# output_max10.net
KiCad netlist of a schematic drawn in EAGLE
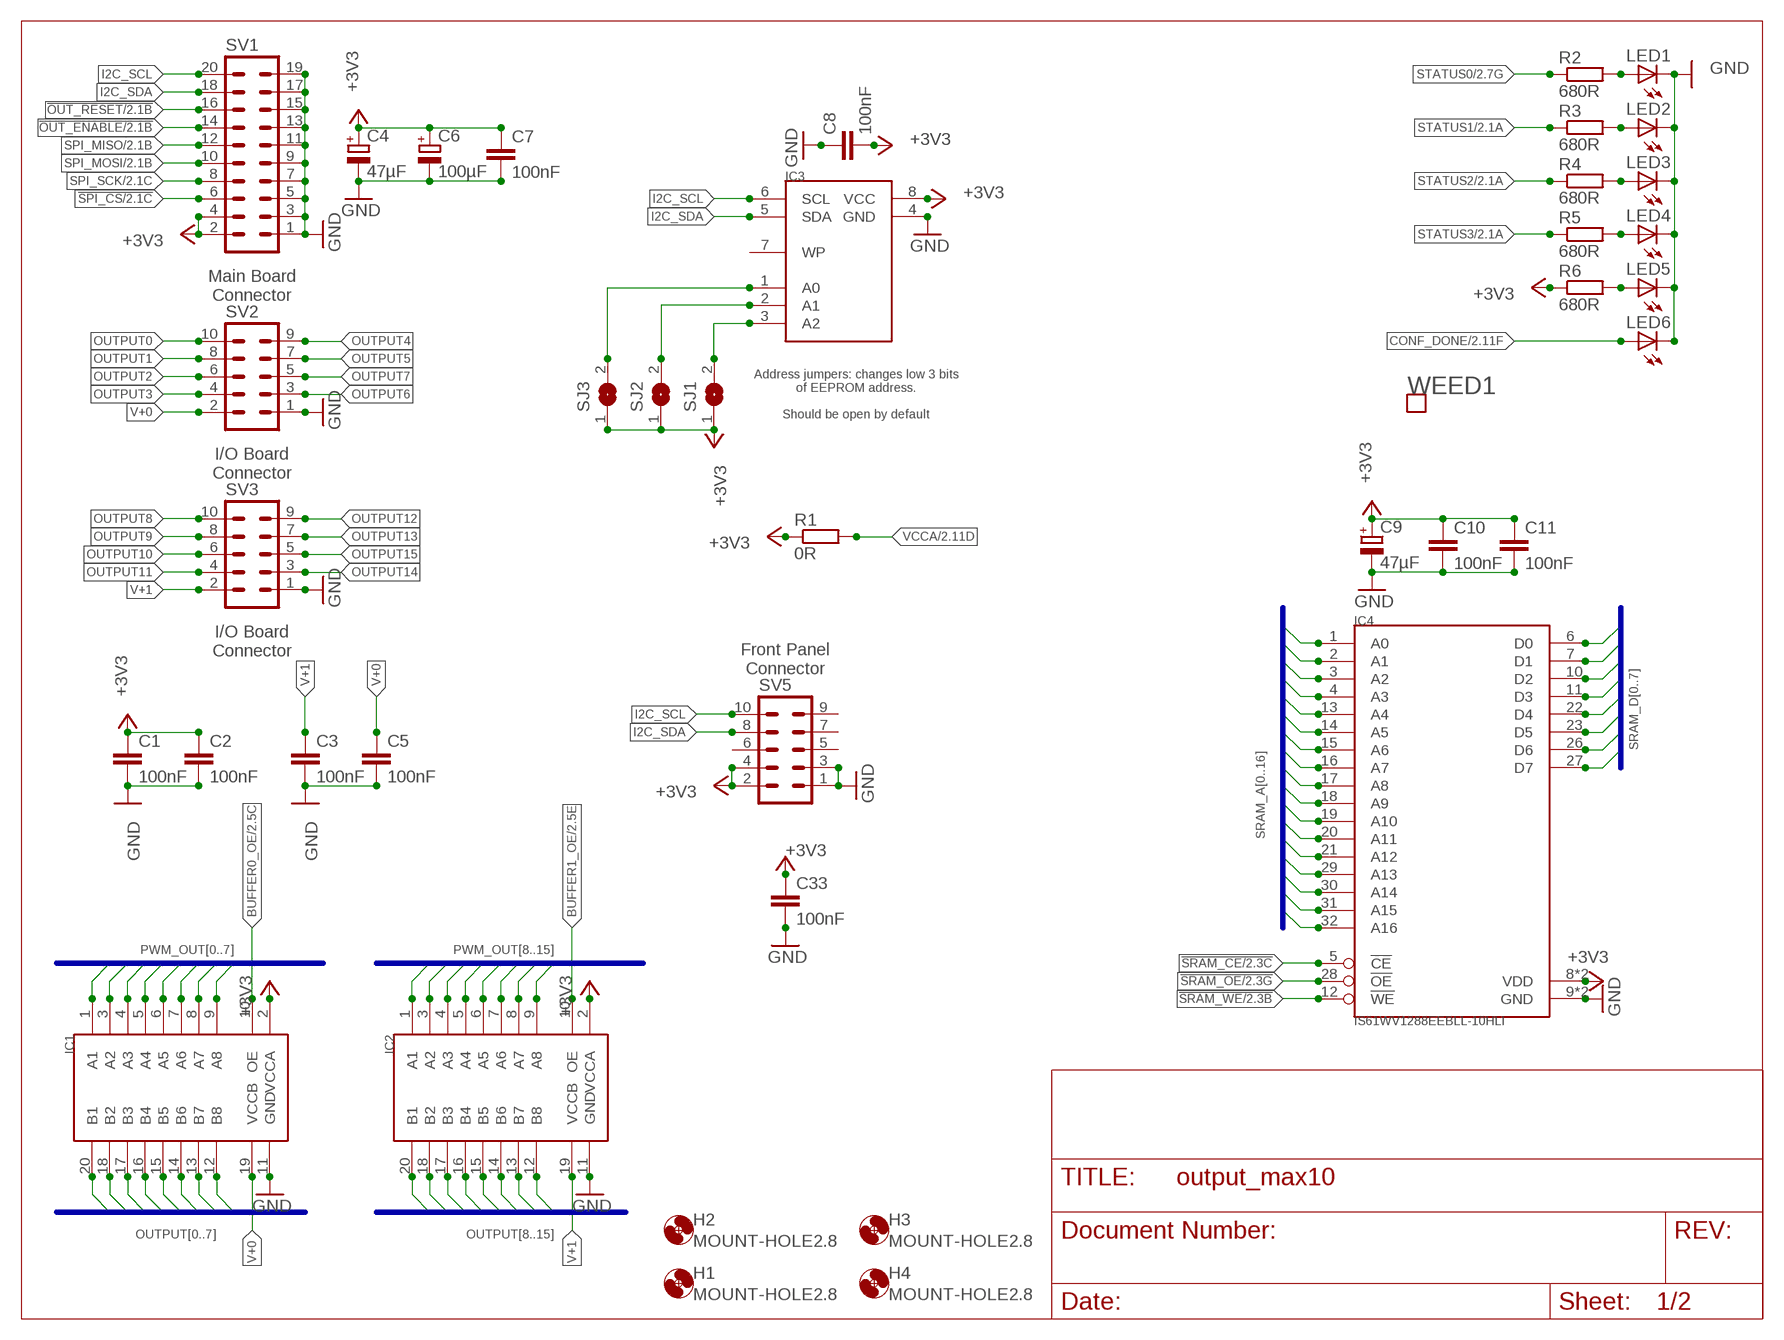
[diagram p0: schematic, sheet 1]
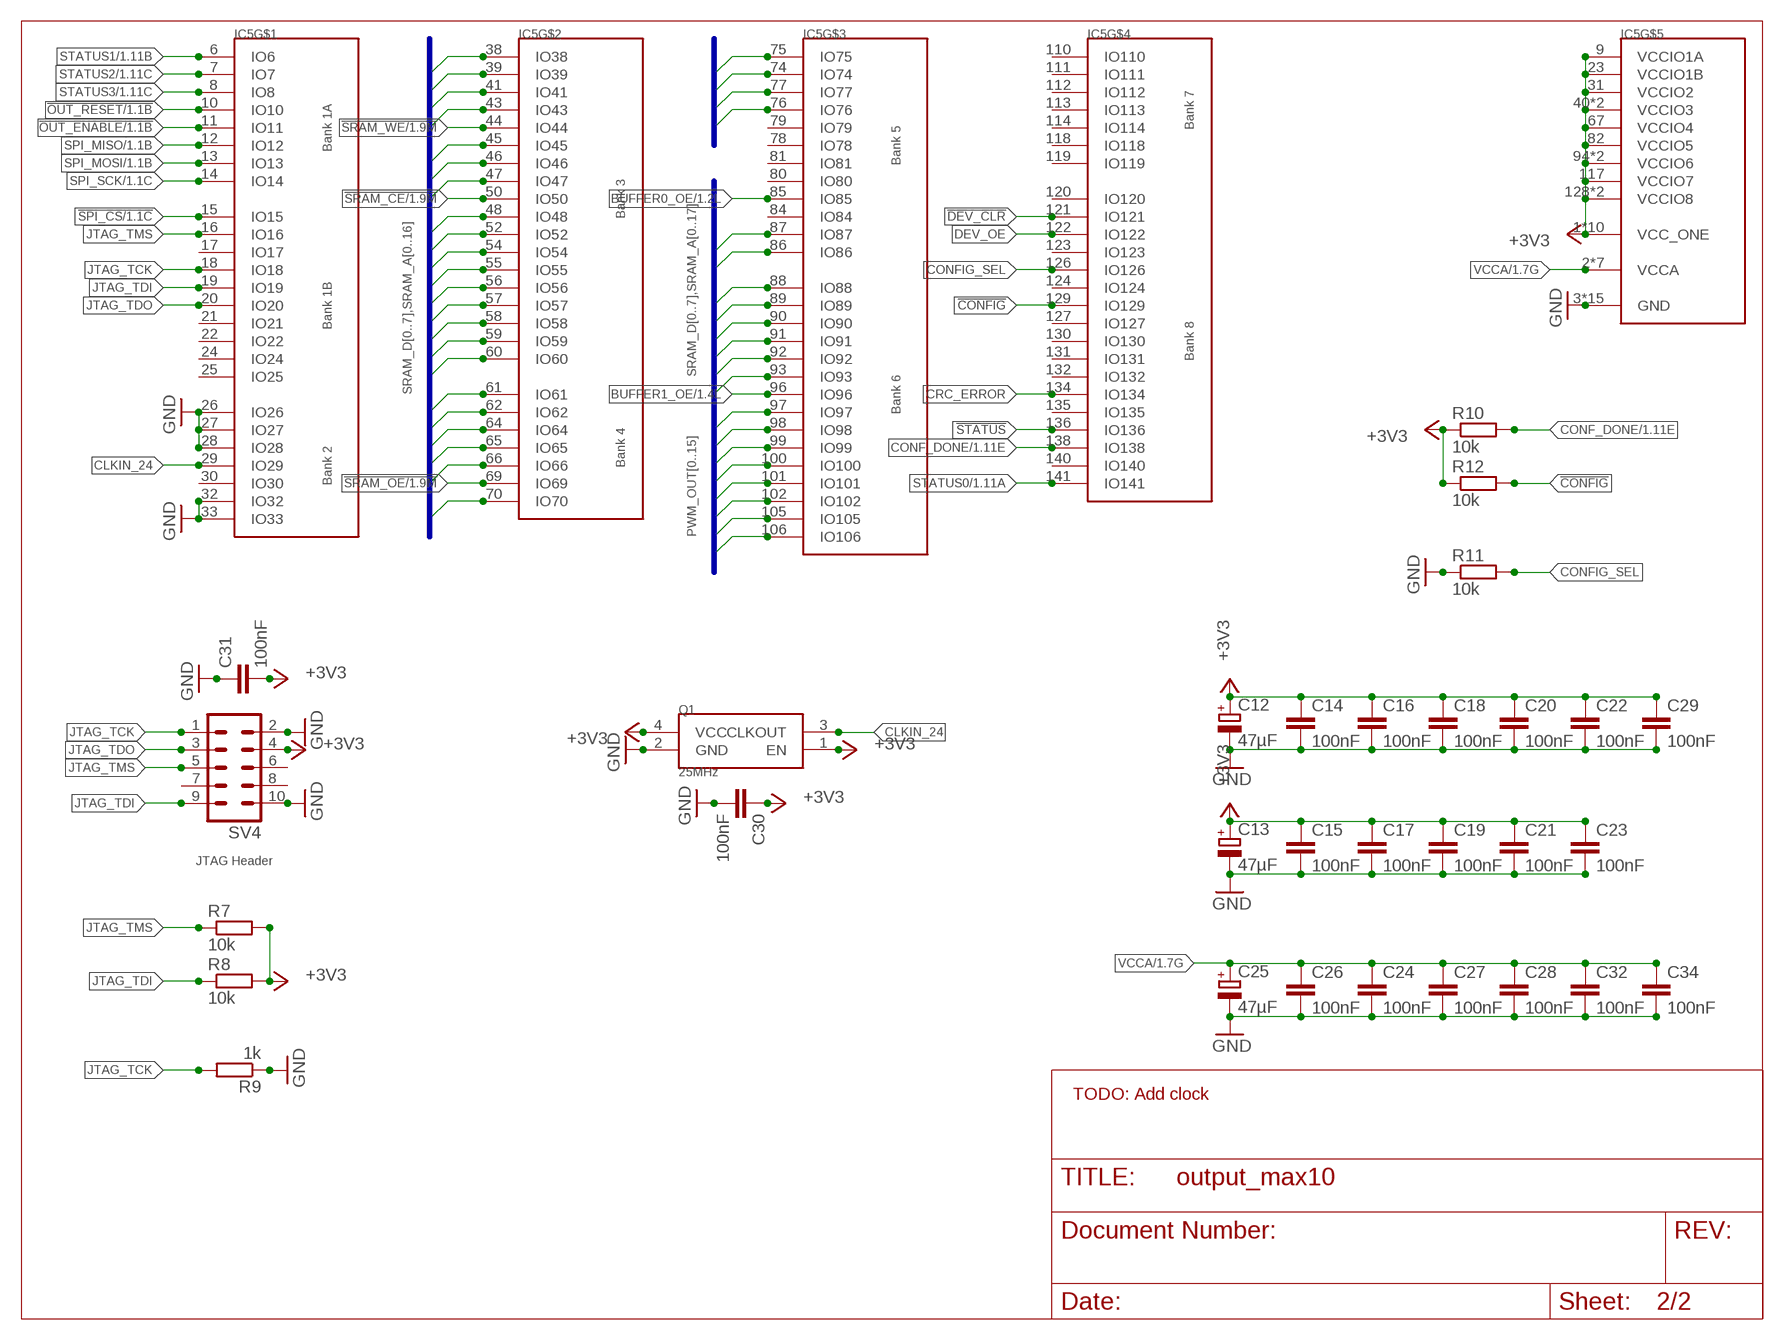
[diagram p1: schematic, sheet 2]

(export (version "E")
  (design (tool "Eeschema 10.0.6"))
  (components
    (comp (ref "C1")
      (value "100nF")
      (footprint "eagle-import:C0805")
      (libsource (lib "eagle-import") (part "C-EUC0805"))
    )
    (comp (ref "C2")
      (value "100nF")
      (footprint "eagle-import:C0805")
      (libsource (lib "eagle-import") (part "C-EUC0805"))
    )
    (comp (ref "C3")
      (value "100nF")
      (footprint "eagle-import:C0805")
      (libsource (lib "eagle-import") (part "C-EUC0805"))
    )
    (comp (ref "C4")
      (value "47µF")
      (footprint "eagle-import:CT7343")
      (libsource (lib "eagle-import") (part "CPOL-EUCT7343"))
    )
    (comp (ref "C5")
      (value "100nF")
      (footprint "eagle-import:C0805")
      (libsource (lib "eagle-import") (part "C-EUC0805"))
    )
    (comp (ref "C6")
      (value "100µF")
      (footprint "eagle-import:CT7343")
      (libsource (lib "eagle-import") (part "CPOL-EUCT7343"))
    )
    (comp (ref "C7")
      (value "100nF")
      (footprint "eagle-import:C0805")
      (libsource (lib "eagle-import") (part "C-EUC0805"))
    )
    (comp (ref "C8")
      (value "100nF")
      (footprint "eagle-import:C0805")
      (libsource (lib "eagle-import") (part "C-EUC0805"))
    )
    (comp (ref "C9")
      (value "47µF")
      (footprint "eagle-import:CT7343")
      (libsource (lib "eagle-import") (part "CPOL-EUCT7343"))
    )
    (comp (ref "C10")
      (value "100nF")
      (footprint "eagle-import:C0805")
      (libsource (lib "eagle-import") (part "C-EUC0805"))
    )
    (comp (ref "C11")
      (value "100nF")
      (footprint "eagle-import:C0805")
      (libsource (lib "eagle-import") (part "C-EUC0805"))
    )
    (comp (ref "C33")
      (value "100nF")
      (footprint "eagle-import:C0805")
      (libsource (lib "eagle-import") (part "C-EUC0805"))
    )
    (comp (ref "H1")
      (value "MOUNT-HOLE2.8")
      (footprint "eagle-import:2,8")
      (libsource (lib "eagle-import") (part "MOUNT-HOLE2.8"))
    )
    (comp (ref "H2")
      (value "MOUNT-HOLE2.8")
      (footprint "eagle-import:2,8")
      (libsource (lib "eagle-import") (part "MOUNT-HOLE2.8"))
    )
    (comp (ref "H3")
      (value "MOUNT-HOLE2.8")
      (footprint "eagle-import:2,8")
      (libsource (lib "eagle-import") (part "MOUNT-HOLE2.8"))
    )
    (comp (ref "H4")
      (value "MOUNT-HOLE2.8")
      (footprint "eagle-import:2,8")
      (libsource (lib "eagle-import") (part "MOUNT-HOLE2.8"))
    )
    (comp (ref "IC1")
      (value "TXB0108TSSOP20")
      (footprint "eagle-import:TSSOP20")
      (libsource (lib "eagle-import") (part "TXB0108TSSOP20"))
    )
    (comp (ref "IC2")
      (value "TXB0108TSSOP20")
      (footprint "eagle-import:TSSOP20")
      (libsource (lib "eagle-import") (part "TXB0108TSSOP20"))
    )
    (comp (ref "IC3")
      (value "AT24C02DSOIC-8")
      (footprint "eagle-import:SOIC8")
      (libsource (lib "eagle-import") (part "AT24C02DSOIC-8"))
    )
    (comp (ref "IC4")
      (value "IS61WV1288EEBLL-10HLI")
      (footprint "eagle-import:TSOP8X16")
      (libsource (lib "eagle-import") (part "IS61WV1288EEBLLTSOP32-I"))
    )
    (comp (ref "LED1")
      (value "LEDCHIPLED_1206")
      (footprint "eagle-import:CHIPLED_1206")
      (libsource (lib "eagle-import") (part "LEDCHIPLED_1206"))
    )
    (comp (ref "LED2")
      (value "LEDCHIPLED_1206")
      (footprint "eagle-import:CHIPLED_1206")
      (libsource (lib "eagle-import") (part "LEDCHIPLED_1206"))
    )
    (comp (ref "LED3")
      (value "LEDCHIPLED_1206")
      (footprint "eagle-import:CHIPLED_1206")
      (libsource (lib "eagle-import") (part "LEDCHIPLED_1206"))
    )
    (comp (ref "LED4")
      (value "LEDCHIPLED_1206")
      (footprint "eagle-import:CHIPLED_1206")
      (libsource (lib "eagle-import") (part "LEDCHIPLED_1206"))
    )
    (comp (ref "LED5")
      (value "LEDCHIPLED_1206")
      (footprint "eagle-import:CHIPLED_1206")
      (libsource (lib "eagle-import") (part "LEDCHIPLED_1206"))
    )
    (comp (ref "LED6")
      (value "LEDCHIPLED_1206")
      (footprint "eagle-import:CHIPLED_1206")
      (libsource (lib "eagle-import") (part "LEDCHIPLED_1206"))
    )
    (comp (ref "R1")
      (value "0R")
      (footprint "eagle-import:R2012")
      (libsource (lib "eagle-import") (part "R-EU_R2012"))
    )
    (comp (ref "R2")
      (value "680R")
      (footprint "eagle-import:M0805")
      (libsource (lib "eagle-import") (part "R-EU_M0805"))
    )
    (comp (ref "R3")
      (value "680R")
      (footprint "eagle-import:M0805")
      (libsource (lib "eagle-import") (part "R-EU_M0805"))
    )
    (comp (ref "R4")
      (value "680R")
      (footprint "eagle-import:M0805")
      (libsource (lib "eagle-import") (part "R-EU_M0805"))
    )
    (comp (ref "R5")
      (value "680R")
      (footprint "eagle-import:M0805")
      (libsource (lib "eagle-import") (part "R-EU_M0805"))
    )
    (comp (ref "R6")
      (value "680R")
      (footprint "eagle-import:M0805")
      (libsource (lib "eagle-import") (part "R-EU_M0805"))
    )
    (comp (ref "SJ1") (value "SJ") (footprint "eagle-import:SJ") (libsource (lib "eagle-import") (part "SJ")))
    (comp (ref "SJ2") (value "SJ") (footprint "eagle-import:SJ") (libsource (lib "eagle-import") (part "SJ")))
    (comp (ref "SJ3") (value "SJ") (footprint "eagle-import:SJ") (libsource (lib "eagle-import") (part "SJ")))
    (comp (ref "SV1")
      (value "MA10-2")
      (footprint "eagle-import:MA10-2")
      (libsource (lib "eagle-import") (part "MA10-2"))
    )
    (comp (ref "SV2")
      (value "MA05-2")
      (footprint "eagle-import:MA05-2")
      (libsource (lib "eagle-import") (part "MA05-2"))
    )
    (comp (ref "SV3")
      (value "MA05-2")
      (footprint "eagle-import:MA05-2")
      (libsource (lib "eagle-import") (part "MA05-2"))
    )
    (comp (ref "SV5")
      (value "MA05-2")
      (footprint "eagle-import:MA05-2")
      (libsource (lib "eagle-import") (part "MA05-2"))
    )
    (comp (ref "WEED1")
      (value "WEED")
      (footprint "eagle-import:DOINK")
      (libsource (lib "eagle-import") (part "WEED"))
    )
    (comp (ref "C12")
      (value "47µF")
      (footprint "eagle-import:CT7343")
      (libsource (lib "eagle-import") (part "CPOL-EUCT7343"))
    )
    (comp (ref "C13")
      (value "47µF")
      (footprint "eagle-import:CT7343")
      (libsource (lib "eagle-import") (part "CPOL-EUCT7343"))
    )
    (comp (ref "C14")
      (value "100nF")
      (footprint "eagle-import:C0805")
      (libsource (lib "eagle-import") (part "C-EUC0805"))
    )
    (comp (ref "C15")
      (value "100nF")
      (footprint "eagle-import:C0805")
      (libsource (lib "eagle-import") (part "C-EUC0805"))
    )
    (comp (ref "C16")
      (value "100nF")
      (footprint "eagle-import:C0805")
      (libsource (lib "eagle-import") (part "C-EUC0805"))
    )
    (comp (ref "C17")
      (value "100nF")
      (footprint "eagle-import:C0805")
      (libsource (lib "eagle-import") (part "C-EUC0805"))
    )
    (comp (ref "C18")
      (value "100nF")
      (footprint "eagle-import:C0805")
      (libsource (lib "eagle-import") (part "C-EUC0805"))
    )
    (comp (ref "C19")
      (value "100nF")
      (footprint "eagle-import:C0805")
      (libsource (lib "eagle-import") (part "C-EUC0805"))
    )
    (comp (ref "C20")
      (value "100nF")
      (footprint "eagle-import:C0805")
      (libsource (lib "eagle-import") (part "C-EUC0805"))
    )
    (comp (ref "C21")
      (value "100nF")
      (footprint "eagle-import:C0805")
      (libsource (lib "eagle-import") (part "C-EUC0805"))
    )
    (comp (ref "C22")
      (value "100nF")
      (footprint "eagle-import:C0805")
      (libsource (lib "eagle-import") (part "C-EUC0805"))
    )
    (comp (ref "C23")
      (value "100nF")
      (footprint "eagle-import:C0805")
      (libsource (lib "eagle-import") (part "C-EUC0805"))
    )
    (comp (ref "C24")
      (value "100nF")
      (footprint "eagle-import:C0805")
      (libsource (lib "eagle-import") (part "C-EUC0805"))
    )
    (comp (ref "C25")
      (value "47µF")
      (footprint "eagle-import:CT7343")
      (libsource (lib "eagle-import") (part "CPOL-EUCT7343"))
    )
    (comp (ref "C26")
      (value "100nF")
      (footprint "eagle-import:C0805")
      (libsource (lib "eagle-import") (part "C-EUC0805"))
    )
    (comp (ref "C27")
      (value "100nF")
      (footprint "eagle-import:C0805")
      (libsource (lib "eagle-import") (part "C-EUC0805"))
    )
    (comp (ref "C28")
      (value "100nF")
      (footprint "eagle-import:C0805")
      (libsource (lib "eagle-import") (part "C-EUC0805"))
    )
    (comp (ref "C29")
      (value "100nF")
      (footprint "eagle-import:C0805")
      (libsource (lib "eagle-import") (part "C-EUC0805"))
    )
    (comp (ref "C30")
      (value "100nF")
      (footprint "eagle-import:C0805")
      (libsource (lib "eagle-import") (part "C-EUC0805"))
    )
    (comp (ref "C31")
      (value "100nF")
      (footprint "eagle-import:C0805")
      (libsource (lib "eagle-import") (part "C-EUC0805"))
    )
    (comp (ref "C32")
      (value "100nF")
      (footprint "eagle-import:C0805")
      (libsource (lib "eagle-import") (part "C-EUC0805"))
    )
    (comp (ref "C34")
      (value "100nF")
      (footprint "eagle-import:C0805")
      (libsource (lib "eagle-import") (part "C-EUC0805"))
    )
    (comp (ref "IC5")
      (value "10M04EQFP144")
      (footprint "eagle-import:EQFP144")
      (fields (field (name "MOUSER") "989-10M04SCE144C8G"))
      (libsource (lib "eagle-import") (part "10M04EQFP144"))
    )
    (comp (ref "Q1")
      (value "25MHz")
      (footprint "eagle-import:VLGA-4")
      (libsource (lib "eagle-import") (part "DSC61XX"))
    )
    (comp (ref "R7")
      (value "10k")
      (footprint "eagle-import:M0805")
      (libsource (lib "eagle-import") (part "R-EU_M0805"))
    )
    (comp (ref "R8")
      (value "10k")
      (footprint "eagle-import:M0805")
      (libsource (lib "eagle-import") (part "R-EU_M0805"))
    )
    (comp (ref "R9")
      (value "1k")
      (footprint "eagle-import:M0805")
      (libsource (lib "eagle-import") (part "R-EU_M0805"))
    )
    (comp (ref "R10")
      (value "10k")
      (footprint "eagle-import:M0805")
      (libsource (lib "eagle-import") (part "R-EU_M0805"))
    )
    (comp (ref "R11")
      (value "10k")
      (footprint "eagle-import:M0805")
      (libsource (lib "eagle-import") (part "R-EU_M0805"))
    )
    (comp (ref "R12")
      (value "10k")
      (footprint "eagle-import:M0805")
      (libsource (lib "eagle-import") (part "R-EU_M0805"))
    )
    (comp (ref "SV4")
      (value "MA05-2")
      (footprint "eagle-import:MA05-2")
      (libsource (lib "eagle-import") (part "MA05-2"))
    )
  )
  (nets
    (net (code "1") (name "+3V3") (class "Default")
      (node (ref "C1") (pin "1") (pinfunction "1_1") (pintype "passive"))
      (node (ref "C10") (pin "1") (pinfunction "1_1") (pintype "passive"))
      (node (ref "C11") (pin "1") (pinfunction "1_1") (pintype "passive"))
      (node (ref "C12") (pin "+") (pinfunction "+_+") (pintype "passive"))
      (node (ref "C13") (pin "+") (pinfunction "+_+") (pintype "passive"))
      (node (ref "C14") (pin "1") (pinfunction "1_1") (pintype "passive"))
      (node (ref "C15") (pin "1") (pinfunction "1_1") (pintype "passive"))
      (node (ref "C16") (pin "1") (pinfunction "1_1") (pintype "passive"))
      (node (ref "C17") (pin "1") (pinfunction "1_1") (pintype "passive"))
      (node (ref "C18") (pin "1") (pinfunction "1_1") (pintype "passive"))
      (node (ref "C19") (pin "1") (pinfunction "1_1") (pintype "passive"))
      (node (ref "C2") (pin "1") (pinfunction "1_1") (pintype "passive"))
      (node (ref "C20") (pin "1") (pinfunction "1_1") (pintype "passive"))
      (node (ref "C21") (pin "1") (pinfunction "1_1") (pintype "passive"))
      (node (ref "C22") (pin "1") (pinfunction "1_1") (pintype "passive"))
      (node (ref "C23") (pin "1") (pinfunction "1_1") (pintype "passive"))
      (node (ref "C29") (pin "1") (pinfunction "1_1") (pintype "passive"))
      (node (ref "C30") (pin "1") (pinfunction "1_1") (pintype "passive"))
      (node (ref "C31") (pin "2") (pinfunction "2_2") (pintype "passive"))
      (node (ref "C33") (pin "1") (pinfunction "1_1") (pintype "passive"))
      (node (ref "C4") (pin "+") (pinfunction "+_+") (pintype "passive"))
      (node (ref "C6") (pin "+") (pinfunction "+_+") (pintype "passive"))
      (node (ref "C7") (pin "1") (pinfunction "1_1") (pintype "passive"))
      (node (ref "C8") (pin "2") (pinfunction "2_2") (pintype "passive"))
      (node (ref "C9") (pin "+") (pinfunction "+_+") (pintype "passive"))
      (node (ref "IC1") (pin "2") (pinfunction "VCCA_2") (pintype "bidirectional"))
      (node (ref "IC2") (pin "2") (pinfunction "VCCA_2") (pintype "bidirectional"))
      (node (ref "IC3") (pin "8") (pinfunction "VCC_8") (pintype "power_in"))
      (node (ref "IC4") (pin "24") (pinfunction "VDD_24") (pintype "power_in"))
      (node (ref "IC4") (pin "8") (pinfunction "VDD_8") (pintype "power_in"))
      (node (ref "IC5") (pin "1") (pinfunction "VCC_ONE_1") (pintype "power_in"))
      (node (ref "IC5") (pin "103") (pinfunction "VCCIO6_103") (pintype "power_in"))
      (node (ref "IC5") (pin "108") (pinfunction "VCC_ONE_108") (pintype "power_in"))
      (node (ref "IC5") (pin "109") (pinfunction "VCC_ONE_109") (pintype "power_in"))
      (node (ref "IC5") (pin "115") (pinfunction "VCC_ONE_115") (pintype "power_in"))
      (node (ref "IC5") (pin "117") (pinfunction "VCCIO7_117") (pintype "power_in"))
      (node (ref "IC5") (pin "128") (pinfunction "VCCIO8_128") (pintype "power_in"))
      (node (ref "IC5") (pin "139") (pinfunction "VCCIO8_139") (pintype "power_in"))
      (node (ref "IC5") (pin "144") (pinfunction "VCC_ONE_144") (pintype "power_in"))
      (node (ref "IC5") (pin "23") (pinfunction "VCCIO1B_23") (pintype "power_in"))
      (node (ref "IC5") (pin "31") (pinfunction "VCCIO2_31") (pintype "power_in"))
      (node (ref "IC5") (pin "36") (pinfunction "VCC_ONE_36") (pintype "power_in"))
      (node (ref "IC5") (pin "37") (pinfunction "VCC_ONE_37") (pintype "power_in"))
      (node (ref "IC5") (pin "40") (pinfunction "VCCIO3_40") (pintype "power_in"))
      (node (ref "IC5") (pin "49") (pinfunction "VCCIO3_49") (pintype "power_in"))
      (node (ref "IC5") (pin "51") (pinfunction "VCC_ONE_51") (pintype "power_in"))
      (node (ref "IC5") (pin "67") (pinfunction "VCCIO4_67") (pintype "power_in"))
      (node (ref "IC5") (pin "72") (pinfunction "VCC_ONE_72") (pintype "power_in"))
      (node (ref "IC5") (pin "73") (pinfunction "VCC_ONE_73") (pintype "power_in"))
      (node (ref "IC5") (pin "82") (pinfunction "VCCIO5_82") (pintype "power_in"))
      (node (ref "IC5") (pin "9") (pinfunction "VCCIO1A_9") (pintype "power_in"))
      (node (ref "IC5") (pin "94") (pinfunction "VCCIO6_94") (pintype "power_in"))
      (node (ref "Q1") (pin "1") (pinfunction "EN_1") (pintype "bidirectional"))
      (node (ref "Q1") (pin "4") (pinfunction "VCC_4") (pintype "power_in"))
      (node (ref "R1") (pin "1") (pinfunction "1_1") (pintype "passive"))
      (node (ref "R10") (pin "1") (pinfunction "1_1") (pintype "passive"))
      (node (ref "R12") (pin "1") (pinfunction "1_1") (pintype "passive"))
      (node (ref "R6") (pin "1") (pinfunction "1_1") (pintype "passive"))
      (node (ref "R7") (pin "2") (pinfunction "2_2") (pintype "passive"))
      (node (ref "R8") (pin "2") (pinfunction "2_2") (pintype "passive"))
      (node (ref "SJ1") (pin "1") (pinfunction "1_1") (pintype "passive"))
      (node (ref "SJ2") (pin "1") (pinfunction "1_1") (pintype "passive"))
      (node (ref "SJ3") (pin "1") (pinfunction "1_1") (pintype "passive"))
      (node (ref "SV1") (pin "2") (pinfunction "2_2") (pintype "passive"))
      (node (ref "SV1") (pin "4") (pinfunction "4_4") (pintype "passive"))
      (node (ref "SV4") (pin "4") (pinfunction "4_4") (pintype "passive"))
      (node (ref "SV5") (pin "2") (pinfunction "2_2") (pintype "passive"))
      (node (ref "SV5") (pin "4") (pinfunction "4_4") (pintype "passive"))
    )
    (net (code "11") (name "BUFFER0_OE") (class "Default")
      (node (ref "IC1") (pin "10") (pinfunction "OE_10") (pintype "bidirectional"))
      (node (ref "IC5") (pin "85") (pinfunction "IO85_85") (pintype "bidirectional"))
    )
    (net (code "12") (name "BUFFER1_OE") (class "Default")
      (node (ref "IC2") (pin "10") (pinfunction "OE_10") (pintype "bidirectional"))
      (node (ref "IC5") (pin "96") (pinfunction "IO96_96") (pintype "bidirectional"))
    )
    (net (code "13") (name "CLKIN_24") (class "Default")
      (node (ref "IC5") (pin "29") (pinfunction "IO29_29") (pintype "bidirectional"))
      (node (ref "Q1") (pin "3") (pinfunction "CLKOUT_3") (pintype "bidirectional"))
    )
    (net (code "14") (name "CONFIG_SEL") (class "Default")
      (node (ref "IC5") (pin "126") (pinfunction "IO126_126") (pintype "bidirectional"))
      (node (ref "R11") (pin "2") (pinfunction "2_2") (pintype "passive"))
    )
    (net (code "15") (name "CONF_DONE") (class "Default")
      (node (ref "IC5") (pin "138") (pinfunction "IO138_138") (pintype "bidirectional"))
      (node (ref "LED6") (pin "A") (pinfunction "A_A") (pintype "passive"))
      (node (ref "R10") (pin "2") (pinfunction "2_2") (pintype "passive"))
    )
    (net (code "16") (name "CRC_ERROR") (class "Default")
      (node (ref "IC5") (pin "134") (pinfunction "IO134_134") (pintype "bidirectional"))
    )
    (net (code "17") (name "DEV_OE") (class "Default")
      (node (ref "IC5") (pin "122") (pinfunction "IO122_122") (pintype "bidirectional"))
    )
    (net (code "18") (name "GND") (class "Default")
      (node (ref "C1") (pin "2") (pinfunction "2_2") (pintype "passive"))
      (node (ref "C10") (pin "2") (pinfunction "2_2") (pintype "passive"))
      (node (ref "C11") (pin "2") (pinfunction "2_2") (pintype "passive"))
      (node (ref "C12") (pin "-") (pinfunction "-_-") (pintype "passive"))
      (node (ref "C13") (pin "-") (pinfunction "-_-") (pintype "passive"))
      (node (ref "C14") (pin "2") (pinfunction "2_2") (pintype "passive"))
      (node (ref "C15") (pin "2") (pinfunction "2_2") (pintype "passive"))
      (node (ref "C16") (pin "2") (pinfunction "2_2") (pintype "passive"))
      (node (ref "C17") (pin "2") (pinfunction "2_2") (pintype "passive"))
      (node (ref "C18") (pin "2") (pinfunction "2_2") (pintype "passive"))
      (node (ref "C19") (pin "2") (pinfunction "2_2") (pintype "passive"))
      (node (ref "C2") (pin "2") (pinfunction "2_2") (pintype "passive"))
      (node (ref "C20") (pin "2") (pinfunction "2_2") (pintype "passive"))
      (node (ref "C21") (pin "2") (pinfunction "2_2") (pintype "passive"))
      (node (ref "C22") (pin "2") (pinfunction "2_2") (pintype "passive"))
      (node (ref "C23") (pin "2") (pinfunction "2_2") (pintype "passive"))
      (node (ref "C24") (pin "2") (pinfunction "2_2") (pintype "passive"))
      (node (ref "C25") (pin "-") (pinfunction "-_-") (pintype "passive"))
      (node (ref "C26") (pin "2") (pinfunction "2_2") (pintype "passive"))
      (node (ref "C27") (pin "2") (pinfunction "2_2") (pintype "passive"))
      (node (ref "C28") (pin "2") (pinfunction "2_2") (pintype "passive"))
      (node (ref "C29") (pin "2") (pinfunction "2_2") (pintype "passive"))
      (node (ref "C3") (pin "2") (pinfunction "2_2") (pintype "passive"))
      (node (ref "C30") (pin "2") (pinfunction "2_2") (pintype "passive"))
      (node (ref "C31") (pin "1") (pinfunction "1_1") (pintype "passive"))
      (node (ref "C32") (pin "2") (pinfunction "2_2") (pintype "passive"))
      (node (ref "C33") (pin "2") (pinfunction "2_2") (pintype "passive"))
      (node (ref "C34") (pin "2") (pinfunction "2_2") (pintype "passive"))
      (node (ref "C4") (pin "-") (pinfunction "-_-") (pintype "passive"))
      (node (ref "C5") (pin "2") (pinfunction "2_2") (pintype "passive"))
      (node (ref "C6") (pin "-") (pinfunction "-_-") (pintype "passive"))
      (node (ref "C7") (pin "2") (pinfunction "2_2") (pintype "passive"))
      (node (ref "C8") (pin "1") (pinfunction "1_1") (pintype "passive"))
      (node (ref "C9") (pin "-") (pinfunction "-_-") (pintype "passive"))
      (node (ref "IC1") (pin "11") (pinfunction "GND_11") (pintype "bidirectional"))
      (node (ref "IC2") (pin "11") (pinfunction "GND_11") (pintype "bidirectional"))
      (node (ref "IC3") (pin "4") (pinfunction "GND_4") (pintype "power_in"))
      (node (ref "IC4") (pin "25") (pinfunction "GND_25") (pintype "power_in"))
      (node (ref "IC4") (pin "9") (pinfunction "GND_9") (pintype "power_in"))
      (node (ref "IC5") (pin "104") (pinfunction "GND_104") (pintype "power_in"))
      (node (ref "IC5") (pin "116") (pinfunction "GND_116") (pintype "power_in"))
      (node (ref "IC5") (pin "125") (pinfunction "GND_125") (pintype "power_in"))
      (node (ref "IC5") (pin "133") (pinfunction "GND_133") (pintype "power_in"))
      (node (ref "IC5") (pin "137") (pinfunction "GND_137") (pintype "power_in"))
      (node (ref "IC5") (pin "142") (pinfunction "GND_142") (pintype "power_in"))
      (node (ref "IC5") (pin "26") (pinfunction "IO26_26") (pintype "bidirectional"))
      (node (ref "IC5") (pin "27") (pinfunction "IO27_27") (pintype "bidirectional"))
      (node (ref "IC5") (pin "28") (pinfunction "IO28_28") (pintype "bidirectional"))
      (node (ref "IC5") (pin "3") (pinfunction "GND_3") (pintype "power_in"))
      (node (ref "IC5") (pin "32") (pinfunction "IO32_32") (pintype "bidirectional"))
      (node (ref "IC5") (pin "33") (pinfunction "IO33_33") (pintype "bidirectional"))
      (node (ref "IC5") (pin "4") (pinfunction "GND_4") (pintype "power_in"))
      (node (ref "IC5") (pin "42") (pinfunction "GND_42") (pintype "power_in"))
      (node (ref "IC5") (pin "53") (pinfunction "GND_53") (pintype "power_in"))
      (node (ref "IC5") (pin "63") (pinfunction "GND_63") (pintype "power_in"))
      (node (ref "IC5") (pin "68") (pinfunction "GND_68") (pintype "power_in"))
      (node (ref "IC5") (pin "83") (pinfunction "GND_83") (pintype "power_in"))
      (node (ref "IC5") (pin "95") (pinfunction "GND_95") (pintype "power_in"))
      (node (ref "IC5") (pin "PAD") (pinfunction "GND_PAD") (pintype "power_in"))
      (node (ref "LED1") (pin "C") (pinfunction "C_C") (pintype "passive"))
      (node (ref "LED2") (pin "C") (pinfunction "C_C") (pintype "passive"))
      (node (ref "LED3") (pin "C") (pinfunction "C_C") (pintype "passive"))
      (node (ref "LED4") (pin "C") (pinfunction "C_C") (pintype "passive"))
      (node (ref "LED5") (pin "C") (pinfunction "C_C") (pintype "passive"))
      (node (ref "LED6") (pin "C") (pinfunction "C_C") (pintype "passive"))
      (node (ref "Q1") (pin "2") (pinfunction "GND_2") (pintype "power_in"))
      (node (ref "R11") (pin "1") (pinfunction "1_1") (pintype "passive"))
      (node (ref "R9") (pin "1") (pinfunction "1_1") (pintype "passive"))
      (node (ref "SV1") (pin "1") (pinfunction "1_1") (pintype "passive"))
      (node (ref "SV1") (pin "11") (pinfunction "11_11") (pintype "passive"))
      (node (ref "SV1") (pin "13") (pinfunction "13_13") (pintype "passive"))
      (node (ref "SV1") (pin "15") (pinfunction "15_15") (pintype "passive"))
      (node (ref "SV1") (pin "17") (pinfunction "17_17") (pintype "passive"))
      (node (ref "SV1") (pin "19") (pinfunction "19_19") (pintype "passive"))
      (node (ref "SV1") (pin "3") (pinfunction "3_3") (pintype "passive"))
      (node (ref "SV1") (pin "5") (pinfunction "5_5") (pintype "passive"))
      (node (ref "SV1") (pin "7") (pinfunction "7_7") (pintype "passive"))
      (node (ref "SV1") (pin "9") (pinfunction "9_9") (pintype "passive"))
      (node (ref "SV2") (pin "1") (pinfunction "1_1") (pintype "passive"))
      (node (ref "SV3") (pin "1") (pinfunction "1_1") (pintype "passive"))
      (node (ref "SV4") (pin "10") (pinfunction "10_10") (pintype "passive"))
      (node (ref "SV4") (pin "2") (pinfunction "2_2") (pintype "passive"))
      (node (ref "SV5") (pin "1") (pinfunction "1_1") (pintype "passive"))
      (node (ref "SV5") (pin "3") (pinfunction "3_3") (pintype "passive"))
    )
    (net (code "19") (name "I2C_SCL") (class "Default")
      (node (ref "IC3") (pin "6") (pinfunction "SCL_6") (pintype "bidirectional"))
      (node (ref "SV1") (pin "20") (pinfunction "20_20") (pintype "passive"))
      (node (ref "SV5") (pin "10") (pinfunction "10_10") (pintype "passive"))
    )
    (net (code "20") (name "I2C_SDA") (class "Default")
      (node (ref "IC3") (pin "5") (pinfunction "SDA_5") (pintype "bidirectional"))
      (node (ref "SV1") (pin "18") (pinfunction "18_18") (pintype "passive"))
      (node (ref "SV5") (pin "8") (pinfunction "8_8") (pintype "passive"))
    )
    (net (code "21") (name "JTAG_TCK") (class "Default")
      (node (ref "IC5") (pin "18") (pinfunction "IO18_18") (pintype "bidirectional"))
      (node (ref "R9") (pin "2") (pinfunction "2_2") (pintype "passive"))
      (node (ref "SV4") (pin "1") (pinfunction "1_1") (pintype "passive"))
    )
    (net (code "22") (name "JTAG_TDI") (class "Default")
      (node (ref "IC5") (pin "19") (pinfunction "IO19_19") (pintype "bidirectional"))
      (node (ref "R8") (pin "1") (pinfunction "1_1") (pintype "passive"))
      (node (ref "SV4") (pin "9") (pinfunction "9_9") (pintype "passive"))
    )
    (net (code "23") (name "JTAG_TDO") (class "Default")
      (node (ref "IC5") (pin "20") (pinfunction "IO20_20") (pintype "bidirectional"))
      (node (ref "SV4") (pin "3") (pinfunction "3_3") (pintype "passive"))
    )
    (net (code "24") (name "JTAG_TMS") (class "Default")
      (node (ref "IC5") (pin "16") (pinfunction "IO16_16") (pintype "bidirectional"))
      (node (ref "R7") (pin "1") (pinfunction "1_1") (pintype "passive"))
      (node (ref "SV4") (pin "5") (pinfunction "5_5") (pintype "passive"))
    )
    (net (code "25") (name "Net-(IC3-A0)") (class "Default")
      (node (ref "IC3") (pin "1") (pinfunction "A0_1") (pintype "bidirectional"))
      (node (ref "SJ3") (pin "2") (pinfunction "2_2") (pintype "passive"))
    )
    (net (code "26") (name "Net-(IC3-A1)") (class "Default")
      (node (ref "IC3") (pin "2") (pinfunction "A1_2") (pintype "bidirectional"))
      (node (ref "SJ2") (pin "2") (pinfunction "2_2") (pintype "passive"))
    )
    (net (code "27") (name "Net-(IC3-A2)") (class "Default")
      (node (ref "IC3") (pin "3") (pinfunction "A2_3") (pintype "bidirectional"))
      (node (ref "SJ1") (pin "2") (pinfunction "2_2") (pintype "passive"))
    )
    (net (code "28") (name "Net-(LED1-PadA)") (class "Default")
      (node (ref "LED1") (pin "A") (pinfunction "A_A") (pintype "passive"))
      (node (ref "R2") (pin "2") (pinfunction "2_2") (pintype "passive"))
    )
    (net (code "29") (name "Net-(LED2-PadA)") (class "Default")
      (node (ref "LED2") (pin "A") (pinfunction "A_A") (pintype "passive"))
      (node (ref "R3") (pin "2") (pinfunction "2_2") (pintype "passive"))
    )
    (net (code "30") (name "Net-(LED3-PadA)") (class "Default")
      (node (ref "LED3") (pin "A") (pinfunction "A_A") (pintype "passive"))
      (node (ref "R4") (pin "2") (pinfunction "2_2") (pintype "passive"))
    )
    (net (code "31") (name "Net-(LED4-PadA)") (class "Default")
      (node (ref "LED4") (pin "A") (pinfunction "A_A") (pintype "passive"))
      (node (ref "R5") (pin "2") (pinfunction "2_2") (pintype "passive"))
    )
    (net (code "32") (name "Net-(LED5-PadA)") (class "Default")
      (node (ref "LED5") (pin "A") (pinfunction "A_A") (pintype "passive"))
      (node (ref "R6") (pin "2") (pinfunction "2_2") (pintype "passive"))
    )
    (net (code "33") (name "OUTPUT0") (class "Default")
      (node (ref "IC1") (pin "20") (pinfunction "B1_20") (pintype "bidirectional"))
      (node (ref "SV2") (pin "10") (pinfunction "10_10") (pintype "passive"))
    )
    (net (code "34") (name "OUTPUT1") (class "Default")
      (node (ref "IC1") (pin "18") (pinfunction "B2_18") (pintype "bidirectional"))
      (node (ref "SV2") (pin "8") (pinfunction "8_8") (pintype "passive"))
    )
    (net (code "35") (name "OUTPUT2") (class "Default")
      (node (ref "IC1") (pin "17") (pinfunction "B3_17") (pintype "bidirectional"))
      (node (ref "SV2") (pin "6") (pinfunction "6_6") (pintype "passive"))
    )
    (net (code "36") (name "OUTPUT3") (class "Default")
      (node (ref "IC1") (pin "16") (pinfunction "B4_16") (pintype "bidirectional"))
      (node (ref "SV2") (pin "4") (pinfunction "4_4") (pintype "passive"))
    )
    (net (code "37") (name "OUTPUT4") (class "Default")
      (node (ref "IC1") (pin "15") (pinfunction "B5_15") (pintype "bidirectional"))
      (node (ref "SV2") (pin "9") (pinfunction "9_9") (pintype "passive"))
    )
    (net (code "38") (name "OUTPUT5") (class "Default")
      (node (ref "IC1") (pin "14") (pinfunction "B6_14") (pintype "bidirectional"))
      (node (ref "SV2") (pin "7") (pinfunction "7_7") (pintype "passive"))
    )
    (net (code "39") (name "OUTPUT6") (class "Default")
      (node (ref "IC1") (pin "13") (pinfunction "B7_13") (pintype "bidirectional"))
      (node (ref "SV2") (pin "3") (pinfunction "3_3") (pintype "passive"))
    )
    (net (code "40") (name "OUTPUT7") (class "Default")
      (node (ref "IC1") (pin "12") (pinfunction "B8_12") (pintype "bidirectional"))
      (node (ref "SV2") (pin "5") (pinfunction "5_5") (pintype "passive"))
    )
    (net (code "41") (name "OUTPUT8") (class "Default")
      (node (ref "IC2") (pin "20") (pinfunction "B1_20") (pintype "bidirectional"))
      (node (ref "SV3") (pin "10") (pinfunction "10_10") (pintype "passive"))
    )
    (net (code "42") (name "OUTPUT9") (class "Default")
      (node (ref "IC2") (pin "18") (pinfunction "B2_18") (pintype "bidirectional"))
      (node (ref "SV3") (pin "8") (pinfunction "8_8") (pintype "passive"))
    )
    (net (code "43") (name "OUTPUT10") (class "Default")
      (node (ref "IC2") (pin "17") (pinfunction "B3_17") (pintype "bidirectional"))
      (node (ref "SV3") (pin "6") (pinfunction "6_6") (pintype "passive"))
    )
    (net (code "44") (name "OUTPUT11") (class "Default")
      (node (ref "IC2") (pin "16") (pinfunction "B4_16") (pintype "bidirectional"))
      (node (ref "SV3") (pin "4") (pinfunction "4_4") (pintype "passive"))
    )
    (net (code "45") (name "OUTPUT12") (class "Default")
      (node (ref "IC2") (pin "15") (pinfunction "B5_15") (pintype "bidirectional"))
      (node (ref "SV3") (pin "9") (pinfunction "9_9") (pintype "passive"))
    )
    (net (code "46") (name "OUTPUT13") (class "Default")
      (node (ref "IC2") (pin "14") (pinfunction "B6_14") (pintype "bidirectional"))
      (node (ref "SV3") (pin "7") (pinfunction "7_7") (pintype "passive"))
    )
    (net (code "47") (name "OUTPUT14") (class "Default")
      (node (ref "IC2") (pin "13") (pinfunction "B7_13") (pintype "bidirectional"))
      (node (ref "SV3") (pin "3") (pinfunction "3_3") (pintype "passive"))
    )
    (net (code "48") (name "OUTPUT15") (class "Default")
      (node (ref "IC2") (pin "12") (pinfunction "B8_12") (pintype "bidirectional"))
      (node (ref "SV3") (pin "5") (pinfunction "5_5") (pintype "passive"))
    )
    (net (code "49") (name "PWM_OUT0") (class "Default")
      (node (ref "IC1") (pin "9") (pinfunction "A8_9") (pintype "bidirectional"))
      (node (ref "IC5") (pin "86") (pinfunction "IO86_86") (pintype "bidirectional"))
    )
    (net (code "50") (name "PWM_OUT1") (class "Default")
      (node (ref "IC1") (pin "8") (pinfunction "A7_8") (pintype "bidirectional"))
      (node (ref "IC5") (pin "87") (pinfunction "IO87_87") (pintype "bidirectional"))
    )
    (net (code "51") (name "PWM_OUT2") (class "Default")
      (node (ref "IC1") (pin "7") (pinfunction "A6_7") (pintype "bidirectional"))
      (node (ref "IC5") (pin "88") (pinfunction "IO88_88") (pintype "bidirectional"))
    )
    (net (code "52") (name "PWM_OUT3") (class "Default")
      (node (ref "IC1") (pin "6") (pinfunction "A5_6") (pintype "bidirectional"))
      (node (ref "IC5") (pin "89") (pinfunction "IO89_89") (pintype "bidirectional"))
    )
    (net (code "53") (name "PWM_OUT4") (class "Default")
      (node (ref "IC1") (pin "5") (pinfunction "A4_5") (pintype "bidirectional"))
      (node (ref "IC5") (pin "90") (pinfunction "IO90_90") (pintype "bidirectional"))
    )
    (net (code "54") (name "PWM_OUT5") (class "Default")
      (node (ref "IC1") (pin "4") (pinfunction "A3_4") (pintype "bidirectional"))
      (node (ref "IC5") (pin "91") (pinfunction "IO91_91") (pintype "bidirectional"))
    )
    (net (code "55") (name "PWM_OUT6") (class "Default")
      (node (ref "IC1") (pin "3") (pinfunction "A2_3") (pintype "bidirectional"))
      (node (ref "IC5") (pin "92") (pinfunction "IO92_92") (pintype "bidirectional"))
    )
    (net (code "56") (name "PWM_OUT7") (class "Default")
      (node (ref "IC1") (pin "1") (pinfunction "A1_1") (pintype "bidirectional"))
      (node (ref "IC5") (pin "93") (pinfunction "IO93_93") (pintype "bidirectional"))
    )
    (net (code "57") (name "PWM_OUT8") (class "Default")
      (node (ref "IC2") (pin "9") (pinfunction "A8_9") (pintype "bidirectional"))
      (node (ref "IC5") (pin "97") (pinfunction "IO97_97") (pintype "bidirectional"))
    )
    (net (code "58") (name "PWM_OUT9") (class "Default")
      (node (ref "IC2") (pin "8") (pinfunction "A7_8") (pintype "bidirectional"))
      (node (ref "IC5") (pin "98") (pinfunction "IO98_98") (pintype "bidirectional"))
    )
    (net (code "59") (name "PWM_OUT10") (class "Default")
      (node (ref "IC2") (pin "7") (pinfunction "A6_7") (pintype "bidirectional"))
      (node (ref "IC5") (pin "99") (pinfunction "IO99_99") (pintype "bidirectional"))
    )
    (net (code "60") (name "PWM_OUT11") (class "Default")
      (node (ref "IC2") (pin "6") (pinfunction "A5_6") (pintype "bidirectional"))
      (node (ref "IC5") (pin "100") (pinfunction "IO100_100") (pintype "bidirectional"))
    )
    (net (code "61") (name "PWM_OUT12") (class "Default")
      (node (ref "IC2") (pin "5") (pinfunction "A4_5") (pintype "bidirectional"))
      (node (ref "IC5") (pin "101") (pinfunction "IO101_101") (pintype "bidirectional"))
    )
    (net (code "62") (name "PWM_OUT13") (class "Default")
      (node (ref "IC2") (pin "4") (pinfunction "A3_4") (pintype "bidirectional"))
      (node (ref "IC5") (pin "102") (pinfunction "IO102_102") (pintype "bidirectional"))
    )
    (net (code "63") (name "PWM_OUT14") (class "Default")
      (node (ref "IC2") (pin "3") (pinfunction "A2_3") (pintype "bidirectional"))
      (node (ref "IC5") (pin "105") (pinfunction "IO105_105") (pintype "bidirectional"))
    )
    (net (code "64") (name "PWM_OUT15") (class "Default")
      (node (ref "IC2") (pin "1") (pinfunction "A1_1") (pintype "bidirectional"))
      (node (ref "IC5") (pin "106") (pinfunction "IO106_106") (pintype "bidirectional"))
    )
    (net (code "65") (name "SPI_MISO") (class "Default")
      (node (ref "IC5") (pin "12") (pinfunction "IO12_12") (pintype "bidirectional"))
      (node (ref "SV1") (pin "12") (pinfunction "12_12") (pintype "passive"))
    )
    (net (code "66") (name "SPI_MOSI") (class "Default")
      (node (ref "IC5") (pin "13") (pinfunction "IO13_13") (pintype "bidirectional"))
      (node (ref "SV1") (pin "10") (pinfunction "10_10") (pintype "passive"))
    )
    (net (code "67") (name "SPI_SCK") (class "Default")
      (node (ref "IC5") (pin "14") (pinfunction "IO14_14") (pintype "bidirectional"))
      (node (ref "SV1") (pin "8") (pinfunction "8_8") (pintype "passive"))
    )
    (net (code "68") (name "SRAM_A0") (class "Default")
      (node (ref "IC4") (pin "1") (pinfunction "A0_1") (pintype "input"))
      (node (ref "IC5") (pin "56") (pinfunction "IO56_56") (pintype "bidirectional"))
    )
    (net (code "69") (name "SRAM_A1") (class "Default")
      (node (ref "IC4") (pin "2") (pinfunction "A1_2") (pintype "input"))
      (node (ref "IC5") (pin "55") (pinfunction "IO55_55") (pintype "bidirectional"))
    )
    (net (code "70") (name "SRAM_A2") (class "Default")
      (node (ref "IC4") (pin "3") (pinfunction "A2_3") (pintype "input"))
      (node (ref "IC5") (pin "54") (pinfunction "IO54_54") (pintype "bidirectional"))
    )
    (net (code "71") (name "SRAM_A3") (class "Default")
      (node (ref "IC4") (pin "4") (pinfunction "A3_4") (pintype "input"))
      (node (ref "IC5") (pin "52") (pinfunction "IO52_52") (pintype "bidirectional"))
    )
    (net (code "72") (name "SRAM_A4") (class "Default")
      (node (ref "IC4") (pin "13") (pinfunction "A4_13") (pintype "input"))
      (node (ref "IC5") (pin "43") (pinfunction "IO43_43") (pintype "bidirectional"))
    )
    (net (code "73") (name "SRAM_A5") (class "Default")
      (node (ref "IC4") (pin "14") (pinfunction "A5_14") (pintype "input"))
      (node (ref "IC5") (pin "41") (pinfunction "IO41_41") (pintype "bidirectional"))
    )
    (net (code "74") (name "SRAM_A6") (class "Default")
      (node (ref "IC4") (pin "15") (pinfunction "A6_15") (pintype "input"))
      (node (ref "IC5") (pin "39") (pinfunction "IO39_39") (pintype "bidirectional"))
    )
    (net (code "75") (name "SRAM_A7") (class "Default")
      (node (ref "IC4") (pin "16") (pinfunction "A7_16") (pintype "input"))
      (node (ref "IC5") (pin "38") (pinfunction "IO38_38") (pintype "bidirectional"))
    )
    (net (code "76") (name "SRAM_A8") (class "Default")
      (node (ref "IC4") (pin "17") (pinfunction "A8_17") (pintype "input"))
      (node (ref "IC5") (pin "57") (pinfunction "IO57_57") (pintype "bidirectional"))
    )
    (net (code "77") (name "SRAM_A9") (class "Default")
      (node (ref "IC4") (pin "18") (pinfunction "A9_18") (pintype "input"))
      (node (ref "IC5") (pin "58") (pinfunction "IO58_58") (pintype "bidirectional"))
    )
    (net (code "78") (name "SRAM_A10") (class "Default")
      (node (ref "IC4") (pin "19") (pinfunction "A10_19") (pintype "input"))
      (node (ref "IC5") (pin "59") (pinfunction "IO59_59") (pintype "bidirectional"))
    )
    (net (code "79") (name "SRAM_A11") (class "Default")
      (node (ref "IC4") (pin "20") (pinfunction "A11_20") (pintype "input"))
      (node (ref "IC5") (pin "60") (pinfunction "IO60_60") (pintype "bidirectional"))
    )
    (net (code "80") (name "SRAM_A12") (class "Default")
      (node (ref "IC4") (pin "21") (pinfunction "A12_21") (pintype "input"))
      (node (ref "IC5") (pin "61") (pinfunction "IO61_61") (pintype "bidirectional"))
    )
    (net (code "81") (name "SRAM_A13") (class "Default")
      (node (ref "IC4") (pin "29") (pinfunction "A13_29") (pintype "input"))
      (node (ref "IC5") (pin "70") (pinfunction "IO70_70") (pintype "bidirectional"))
    )
    (net (code "82") (name "SRAM_A14") (class "Default")
      (node (ref "IC4") (pin "30") (pinfunction "A14_30") (pintype "input"))
      (node (ref "IC5") (pin "76") (pinfunction "IO76_76") (pintype "bidirectional"))
    )
    (net (code "83") (name "SRAM_A15") (class "Default")
      (node (ref "IC4") (pin "31") (pinfunction "A15_31") (pintype "input"))
      (node (ref "IC5") (pin "75") (pinfunction "IO75_75") (pintype "bidirectional"))
    )
    (net (code "84") (name "SRAM_A16") (class "Default")
      (node (ref "IC4") (pin "32") (pinfunction "A16_32") (pintype "input"))
      (node (ref "IC5") (pin "74") (pinfunction "IO74_74") (pintype "bidirectional"))
    )
    (net (code "85") (name "SRAM_D0") (class "Default")
      (node (ref "IC4") (pin "6") (pinfunction "D0_6") (pintype "bidirectional"))
      (node (ref "IC5") (pin "48") (pinfunction "IO48_48") (pintype "bidirectional"))
    )
    (net (code "86") (name "SRAM_D1") (class "Default")
      (node (ref "IC4") (pin "7") (pinfunction "D1_7") (pintype "bidirectional"))
      (node (ref "IC5") (pin "47") (pinfunction "IO47_47") (pintype "bidirectional"))
    )
    (net (code "87") (name "SRAM_D2") (class "Default")
      (node (ref "IC4") (pin "10") (pinfunction "D2_10") (pintype "bidirectional"))
      (node (ref "IC5") (pin "46") (pinfunction "IO46_46") (pintype "bidirectional"))
    )
    (net (code "88") (name "SRAM_D3") (class "Default")
      (node (ref "IC4") (pin "11") (pinfunction "D3_11") (pintype "bidirectional"))
      (node (ref "IC5") (pin "45") (pinfunction "IO45_45") (pintype "bidirectional"))
    )
    (net (code "89") (name "SRAM_D4") (class "Default")
      (node (ref "IC4") (pin "22") (pinfunction "D4_22") (pintype "bidirectional"))
      (node (ref "IC5") (pin "62") (pinfunction "IO62_62") (pintype "bidirectional"))
    )
    (net (code "90") (name "SRAM_D5") (class "Default")
      (node (ref "IC4") (pin "23") (pinfunction "D5_23") (pintype "bidirectional"))
      (node (ref "IC5") (pin "64") (pinfunction "IO64_64") (pintype "bidirectional"))
    )
    (net (code "91") (name "SRAM_D6") (class "Default")
      (node (ref "IC4") (pin "26") (pinfunction "D6_26") (pintype "bidirectional"))
      (node (ref "IC5") (pin "65") (pinfunction "IO65_65") (pintype "bidirectional"))
    )
    (net (code "92") (name "SRAM_D7") (class "Default")
      (node (ref "IC4") (pin "27") (pinfunction "D7_27") (pintype "bidirectional"))
      (node (ref "IC5") (pin "66") (pinfunction "IO66_66") (pintype "bidirectional"))
    )
    (net (code "93") (name "STATUS0") (class "Default")
      (node (ref "IC5") (pin "141") (pinfunction "IO141_141") (pintype "bidirectional"))
      (node (ref "R2") (pin "1") (pinfunction "1_1") (pintype "passive"))
    )
    (net (code "94") (name "STATUS1") (class "Default")
      (node (ref "IC5") (pin "6") (pinfunction "IO6_6") (pintype "bidirectional"))
      (node (ref "R3") (pin "1") (pinfunction "1_1") (pintype "passive"))
    )
    (net (code "95") (name "STATUS2") (class "Default")
      (node (ref "IC5") (pin "7") (pinfunction "IO7_7") (pintype "bidirectional"))
      (node (ref "R4") (pin "1") (pinfunction "1_1") (pintype "passive"))
    )
    (net (code "96") (name "STATUS3") (class "Default")
      (node (ref "IC5") (pin "8") (pinfunction "IO8_8") (pintype "bidirectional"))
      (node (ref "R5") (pin "1") (pinfunction "1_1") (pintype "passive"))
    )
    (net (code "97") (name "V+0") (class "Default")
      (node (ref "C5") (pin "1") (pinfunction "1_1") (pintype "passive"))
      (node (ref "IC1") (pin "19") (pinfunction "VCCB_19") (pintype "bidirectional"))
      (node (ref "SV2") (pin "2") (pinfunction "2_2") (pintype "passive"))
    )
    (net (code "98") (name "V+1") (class "Default")
      (node (ref "C3") (pin "1") (pinfunction "1_1") (pintype "passive"))
      (node (ref "IC2") (pin "19") (pinfunction "VCCB_19") (pintype "bidirectional"))
      (node (ref "SV3") (pin "2") (pinfunction "2_2") (pintype "passive"))
    )
    (net (code "99") (name "VCCA") (class "Default")
      (node (ref "C24") (pin "1") (pinfunction "1_1") (pintype "passive"))
      (node (ref "C25") (pin "+") (pinfunction "+_+") (pintype "passive"))
      (node (ref "C26") (pin "1") (pinfunction "1_1") (pintype "passive"))
      (node (ref "C27") (pin "1") (pinfunction "1_1") (pintype "passive"))
      (node (ref "C28") (pin "1") (pinfunction "1_1") (pintype "passive"))
      (node (ref "C32") (pin "1") (pinfunction "1_1") (pintype "passive"))
      (node (ref "C34") (pin "1") (pinfunction "1_1") (pintype "passive"))
      (node (ref "IC5") (pin "107") (pinfunction "VCCA_107") (pintype "power_in"))
      (node (ref "IC5") (pin "143") (pinfunction "VCCA_143") (pintype "power_in"))
      (node (ref "IC5") (pin "2") (pinfunction "VCCA_2") (pintype "power_in"))
      (node (ref "IC5") (pin "34") (pinfunction "VCCA_34") (pintype "power_in"))
      (node (ref "IC5") (pin "35") (pinfunction "VCCA_35") (pintype "power_in"))
      (node (ref "IC5") (pin "5") (pinfunction "VCCA_5") (pintype "power_in"))
      (node (ref "IC5") (pin "71") (pinfunction "VCCA_71") (pintype "power_in"))
      (node (ref "R1") (pin "2") (pinfunction "2_2") (pintype "passive"))
    )
    (net (code "100") (name "unconnected-(IC3-WP-Pad7)") (class "Default")
      (node (ref "IC3") (pin "7") (pinfunction "WP_7") (pintype "bidirectional"))
    )
    (net (code "101") (name "unconnected-(IC5A-IO17-Pad17)") (class "Default")
      (node (ref "IC5") (pin "17") (pinfunction "IO17_17") (pintype "bidirectional"))
    )
    (net (code "102") (name "unconnected-(IC5A-IO21-Pad21)") (class "Default")
      (node (ref "IC5") (pin "21") (pinfunction "IO21_21") (pintype "bidirectional"))
    )
    (net (code "103") (name "unconnected-(IC5A-IO22-Pad22)") (class "Default")
      (node (ref "IC5") (pin "22") (pinfunction "IO22_22") (pintype "bidirectional"))
    )
    (net (code "104") (name "unconnected-(IC5A-IO24-Pad24)") (class "Default")
      (node (ref "IC5") (pin "24") (pinfunction "IO24_24") (pintype "bidirectional"))
    )
    (net (code "105") (name "unconnected-(IC5A-IO25-Pad25)") (class "Default")
      (node (ref "IC5") (pin "25") (pinfunction "IO25_25") (pintype "bidirectional"))
    )
    (net (code "106") (name "unconnected-(IC5A-IO30-Pad30)") (class "Default")
      (node (ref "IC5") (pin "30") (pinfunction "IO30_30") (pintype "bidirectional"))
    )
    (net (code "107") (name "unconnected-(IC5C-IO77-Pad77)") (class "Default")
      (node (ref "IC5") (pin "77") (pinfunction "IO77_77") (pintype "bidirectional"))
    )
    (net (code "108") (name "unconnected-(IC5C-IO78-Pad78)") (class "Default")
      (node (ref "IC5") (pin "78") (pinfunction "IO78_78") (pintype "bidirectional"))
    )
    (net (code "109") (name "unconnected-(IC5C-IO79-Pad79)") (class "Default")
      (node (ref "IC5") (pin "79") (pinfunction "IO79_79") (pintype "bidirectional"))
    )
    (net (code "110") (name "unconnected-(IC5C-IO80-Pad80)") (class "Default")
      (node (ref "IC5") (pin "80") (pinfunction "IO80_80") (pintype "bidirectional"))
    )
    (net (code "111") (name "unconnected-(IC5C-IO81-Pad81)") (class "Default")
      (node (ref "IC5") (pin "81") (pinfunction "IO81_81") (pintype "bidirectional"))
    )
    (net (code "112") (name "unconnected-(IC5C-IO84-Pad84)") (class "Default")
      (node (ref "IC5") (pin "84") (pinfunction "IO84_84") (pintype "bidirectional"))
    )
    (net (code "113") (name "unconnected-(IC5D-IO110-Pad110)") (class "Default")
      (node (ref "IC5") (pin "110") (pinfunction "IO110_110") (pintype "bidirectional"))
    )
    (net (code "114") (name "unconnected-(IC5D-IO111-Pad111)") (class "Default")
      (node (ref "IC5") (pin "111") (pinfunction "IO111_111") (pintype "bidirectional"))
    )
    (net (code "115") (name "unconnected-(IC5D-IO112-Pad112)") (class "Default")
      (node (ref "IC5") (pin "112") (pinfunction "IO112_112") (pintype "bidirectional"))
    )
    (net (code "116") (name "unconnected-(IC5D-IO113-Pad113)") (class "Default")
      (node (ref "IC5") (pin "113") (pinfunction "IO113_113") (pintype "bidirectional"))
    )
    (net (code "117") (name "unconnected-(IC5D-IO114-Pad114)") (class "Default")
      (node (ref "IC5") (pin "114") (pinfunction "IO114_114") (pintype "bidirectional"))
    )
    (net (code "118") (name "unconnected-(IC5D-IO118-Pad118)") (class "Default")
      (node (ref "IC5") (pin "118") (pinfunction "IO118_118") (pintype "bidirectional"))
    )
    (net (code "119") (name "unconnected-(IC5D-IO119-Pad119)") (class "Default")
      (node (ref "IC5") (pin "119") (pinfunction "IO119_119") (pintype "bidirectional"))
    )
    (net (code "120") (name "unconnected-(IC5D-IO120-Pad120)") (class "Default")
      (node (ref "IC5") (pin "120") (pinfunction "IO120_120") (pintype "bidirectional"))
    )
    (net (code "121") (name "unconnected-(IC5D-IO123-Pad123)") (class "Default")
      (node (ref "IC5") (pin "123") (pinfunction "IO123_123") (pintype "bidirectional"))
    )
    (net (code "122") (name "unconnected-(IC5D-IO124-Pad124)") (class "Default")
      (node (ref "IC5") (pin "124") (pinfunction "IO124_124") (pintype "bidirectional"))
    )
    (net (code "123") (name "unconnected-(IC5D-IO127-Pad127)") (class "Default")
      (node (ref "IC5") (pin "127") (pinfunction "IO127_127") (pintype "bidirectional"))
    )
    (net (code "124") (name "unconnected-(IC5D-IO130-Pad130)") (class "Default")
      (node (ref "IC5") (pin "130") (pinfunction "IO130_130") (pintype "bidirectional"))
    )
    (net (code "125") (name "unconnected-(IC5D-IO131-Pad131)") (class "Default")
      (node (ref "IC5") (pin "131") (pinfunction "IO131_131") (pintype "bidirectional"))
    )
    (net (code "126") (name "unconnected-(IC5D-IO132-Pad132)") (class "Default")
      (node (ref "IC5") (pin "132") (pinfunction "IO132_132") (pintype "bidirectional"))
    )
    (net (code "127") (name "unconnected-(IC5D-IO135-Pad135)") (class "Default")
      (node (ref "IC5") (pin "135") (pinfunction "IO135_135") (pintype "bidirectional"))
    )
    (net (code "128") (name "unconnected-(IC5D-IO140-Pad140)") (class "Default")
      (node (ref "IC5") (pin "140") (pinfunction "IO140_140") (pintype "bidirectional"))
    )
    (net (code "129") (name "unconnected-(SV4-Pad6)") (class "Default")
      (node (ref "SV4") (pin "6") (pinfunction "6_6") (pintype "passive"))
    )
    (net (code "130") (name "unconnected-(SV4-Pad7)") (class "Default")
      (node (ref "SV4") (pin "7") (pinfunction "7_7") (pintype "passive"))
    )
    (net (code "131") (name "unconnected-(SV4-Pad8)") (class "Default")
      (node (ref "SV4") (pin "8") (pinfunction "8_8") (pintype "passive"))
    )
    (net (code "132") (name "unconnected-(SV5-Pad5)") (class "Default")
      (node (ref "SV5") (pin "5") (pinfunction "5_5") (pintype "passive"))
    )
    (net (code "133") (name "unconnected-(SV5-Pad6)") (class "Default")
      (node (ref "SV5") (pin "6") (pinfunction "6_6") (pintype "passive"))
    )
    (net (code "134") (name "unconnected-(SV5-Pad7)") (class "Default")
      (node (ref "SV5") (pin "7") (pinfunction "7_7") (pintype "passive"))
    )
    (net (code "135") (name "unconnected-(SV5-Pad9)") (class "Default")
      (node (ref "SV5") (pin "9") (pinfunction "9_9") (pintype "passive"))
    )
    (net (code "136") (name "~{CONFIG}") (class "Default")
      (node (ref "IC5") (pin "129") (pinfunction "IO129_129") (pintype "bidirectional"))
      (node (ref "R12") (pin "2") (pinfunction "2_2") (pintype "passive"))
    )
    (net (code "137") (name "~{DEV_CLR}") (class "Default")
      (node (ref "IC5") (pin "121") (pinfunction "IO121_121") (pintype "bidirectional"))
    )
    (net (code "138") (name "~{OUT_ENABLE}") (class "Default")
      (node (ref "IC5") (pin "11") (pinfunction "IO11_11") (pintype "bidirectional"))
      (node (ref "SV1") (pin "14") (pinfunction "14_14") (pintype "passive"))
    )
    (net (code "139") (name "~{OUT_RESET}") (class "Default")
      (node (ref "IC5") (pin "10") (pinfunction "IO10_10") (pintype "bidirectional"))
      (node (ref "SV1") (pin "16") (pinfunction "16_16") (pintype "passive"))
    )
    (net (code "140") (name "~{SPI_CS}") (class "Default")
      (node (ref "IC5") (pin "15") (pinfunction "IO15_15") (pintype "bidirectional"))
      (node (ref "SV1") (pin "6") (pinfunction "6_6") (pintype "passive"))
    )
    (net (code "141") (name "~{SRAM_CE}") (class "Default")
      (node (ref "IC4") (pin "5") (pinfunction "~{CE}_5") (pintype "input"))
      (node (ref "IC5") (pin "50") (pinfunction "IO50_50") (pintype "bidirectional"))
    )
    (net (code "142") (name "~{SRAM_OE}") (class "Default")
      (node (ref "IC4") (pin "28") (pinfunction "~{OE}_28") (pintype "input"))
      (node (ref "IC5") (pin "69") (pinfunction "IO69_69") (pintype "bidirectional"))
    )
    (net (code "143") (name "~{SRAM_WE}") (class "Default")
      (node (ref "IC4") (pin "12") (pinfunction "~{WE}_12") (pintype "input"))
      (node (ref "IC5") (pin "44") (pinfunction "IO44_44") (pintype "bidirectional"))
    )
    (net (code "144") (name "~{STATUS}") (class "Default")
      (node (ref "IC5") (pin "136") (pinfunction "IO136_136") (pintype "bidirectional"))
    )
  )
)
